# Analogue_slider_board.net
KiCad netlist of a schematic drawn in EAGLE
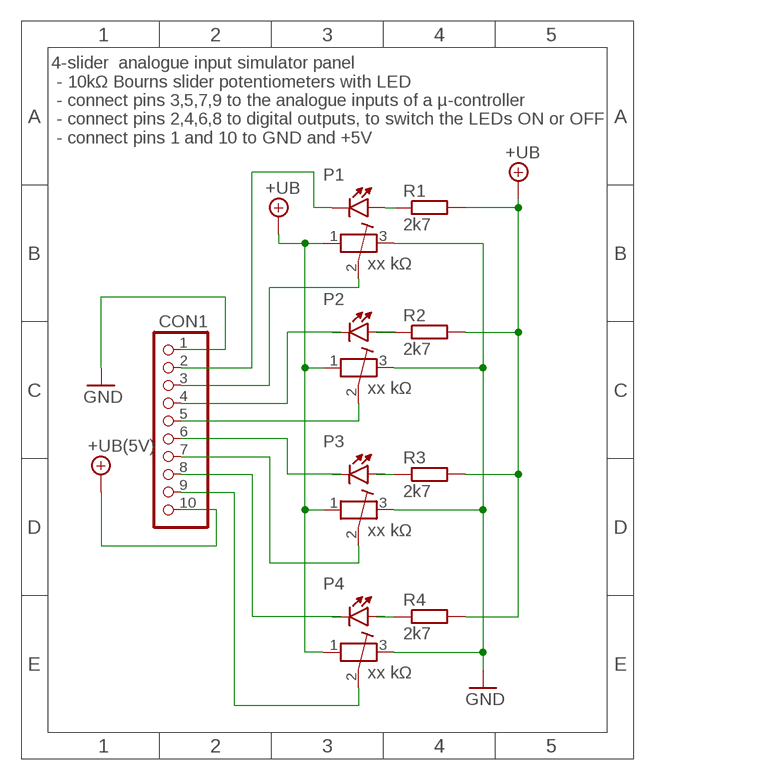
[diagram p0: schematic, sheet 1]

(export (version "E")
  (design (tool "Eeschema 10.0.6"))
  (components
    (comp (ref "CON1")
      (value "PINHD-1X10")
      (footprint "eagle-import:1X10")
      (libsource (lib "eagle-import") (part "PINHD-1X10"))
    )
    (comp (ref "P1")
      (value "10kΩ")
      (footprint "eagle-import:SLIDER_POT_60_WLED")
      (libsource (lib "eagle-import") (part "SLIDER-POTENTIOMETER-60MM-WLED"))
    )
    (comp (ref "P2")
      (value "10kΩ")
      (footprint "eagle-import:SLIDER_POT_60_WLED")
      (libsource (lib "eagle-import") (part "SLIDER-POTENTIOMETER-60MM-WLED"))
    )
    (comp (ref "P3")
      (value "10kΩ")
      (footprint "eagle-import:SLIDER_POT_60_WLED")
      (libsource (lib "eagle-import") (part "SLIDER-POTENTIOMETER-60MM-WLED"))
    )
    (comp (ref "P4")
      (value "10kΩ")
      (footprint "eagle-import:SLIDER_POT_60_WLED")
      (libsource (lib "eagle-import") (part "SLIDER-POTENTIOMETER-60MM-WLED"))
    )
    (comp (ref "R1")
      (value "2k7")
      (footprint "eagle-import:0204_7")
      (libsource (lib "eagle-import") (part "R-EU_0204/7"))
    )
    (comp (ref "R2")
      (value "2k7")
      (footprint "eagle-import:0204_7")
      (libsource (lib "eagle-import") (part "R-EU_0204/7"))
    )
    (comp (ref "R3")
      (value "2k7")
      (footprint "eagle-import:0204_7")
      (libsource (lib "eagle-import") (part "R-EU_0204/7"))
    )
    (comp (ref "R4")
      (value "2k7")
      (footprint "eagle-import:0204_7")
      (libsource (lib "eagle-import") (part "R-EU_0204/7"))
    )
  )
  (nets
    (net (code "1") (name "+UB") (class "Default")
      (node (ref "CON1") (pin "10") (pinfunction "10_10") (pintype "passive"))
      (node (ref "P1") (pin "1") (pinfunction "1_1") (pintype "bidirectional"))
      (node (ref "P2") (pin "1") (pinfunction "1_1") (pintype "bidirectional"))
      (node (ref "P3") (pin "1") (pinfunction "1_1") (pintype "bidirectional"))
      (node (ref "P4") (pin "1") (pinfunction "1_1") (pintype "bidirectional"))
      (node (ref "R1") (pin "2") (pinfunction "2_2") (pintype "passive"))
      (node (ref "R2") (pin "2") (pinfunction "2_2") (pintype "passive"))
      (node (ref "R3") (pin "2") (pinfunction "2_2") (pintype "passive"))
      (node (ref "R4") (pin "2") (pinfunction "2_2") (pintype "passive"))
    )
    (net (code "2") (name "GND") (class "Default")
      (node (ref "CON1") (pin "1") (pinfunction "1_1") (pintype "passive"))
      (node (ref "P1") (pin "3") (pinfunction "3_3") (pintype "bidirectional"))
      (node (ref "P2") (pin "3") (pinfunction "3_3") (pintype "bidirectional"))
      (node (ref "P3") (pin "3") (pinfunction "3_3") (pintype "bidirectional"))
      (node (ref "P4") (pin "3") (pinfunction "3_3") (pintype "bidirectional"))
    )
    (net (code "3") (name "Net-(CON1-Pad3)") (class "Default")
      (node (ref "CON1") (pin "3") (pinfunction "3_3") (pintype "passive"))
      (node (ref "P1") (pin "2") (pinfunction "2_2") (pintype "bidirectional"))
    )
    (net (code "4") (name "Net-(CON1-Pad5)") (class "Default")
      (node (ref "CON1") (pin "5") (pinfunction "5_5") (pintype "passive"))
      (node (ref "P2") (pin "2") (pinfunction "2_2") (pintype "bidirectional"))
    )
    (net (code "5") (name "Net-(CON1-Pad7)") (class "Default")
      (node (ref "CON1") (pin "7") (pinfunction "7_7") (pintype "passive"))
      (node (ref "P3") (pin "2") (pinfunction "2_2") (pintype "bidirectional"))
    )
    (net (code "6") (name "Net-(CON1-Pad9)") (class "Default")
      (node (ref "CON1") (pin "9") (pinfunction "9_9") (pintype "passive"))
      (node (ref "P4") (pin "2") (pinfunction "2_2") (pintype "bidirectional"))
    )
    (net (code "7") (name "Net-(P1-B(+))") (class "Default")
      (node (ref "P1") (pin "B") (pinfunction "B(+)_B") (pintype "bidirectional"))
      (node (ref "R1") (pin "1") (pinfunction "1_1") (pintype "passive"))
    )
    (net (code "8") (name "Net-(P1-E(-))") (class "Default")
      (node (ref "CON1") (pin "2") (pinfunction "2_2") (pintype "passive"))
      (node (ref "P1") (pin "E") (pinfunction "E(-)_E") (pintype "bidirectional"))
    )
    (net (code "9") (name "Net-(P2-B(+))") (class "Default")
      (node (ref "P2") (pin "B") (pinfunction "B(+)_B") (pintype "bidirectional"))
      (node (ref "R2") (pin "1") (pinfunction "1_1") (pintype "passive"))
    )
    (net (code "10") (name "Net-(P2-E(-))") (class "Default")
      (node (ref "CON1") (pin "4") (pinfunction "4_4") (pintype "passive"))
      (node (ref "P2") (pin "E") (pinfunction "E(-)_E") (pintype "bidirectional"))
    )
    (net (code "11") (name "Net-(P3-B(+))") (class "Default")
      (node (ref "P3") (pin "B") (pinfunction "B(+)_B") (pintype "bidirectional"))
      (node (ref "R3") (pin "1") (pinfunction "1_1") (pintype "passive"))
    )
    (net (code "12") (name "Net-(P3-E(-))") (class "Default")
      (node (ref "CON1") (pin "6") (pinfunction "6_6") (pintype "passive"))
      (node (ref "P3") (pin "E") (pinfunction "E(-)_E") (pintype "bidirectional"))
    )
    (net (code "13") (name "Net-(P4-B(+))") (class "Default")
      (node (ref "P4") (pin "B") (pinfunction "B(+)_B") (pintype "bidirectional"))
      (node (ref "R4") (pin "1") (pinfunction "1_1") (pintype "passive"))
    )
    (net (code "14") (name "Net-(P4-E(-))") (class "Default")
      (node (ref "CON1") (pin "8") (pinfunction "8_8") (pintype "passive"))
      (node (ref "P4") (pin "E") (pinfunction "E(-)_E") (pintype "bidirectional"))
    )
  )
)
